# TP2_EJ1_CIRCUIT1_PCB.net
KiCad netlist of a schematic drawn in Altium Designer
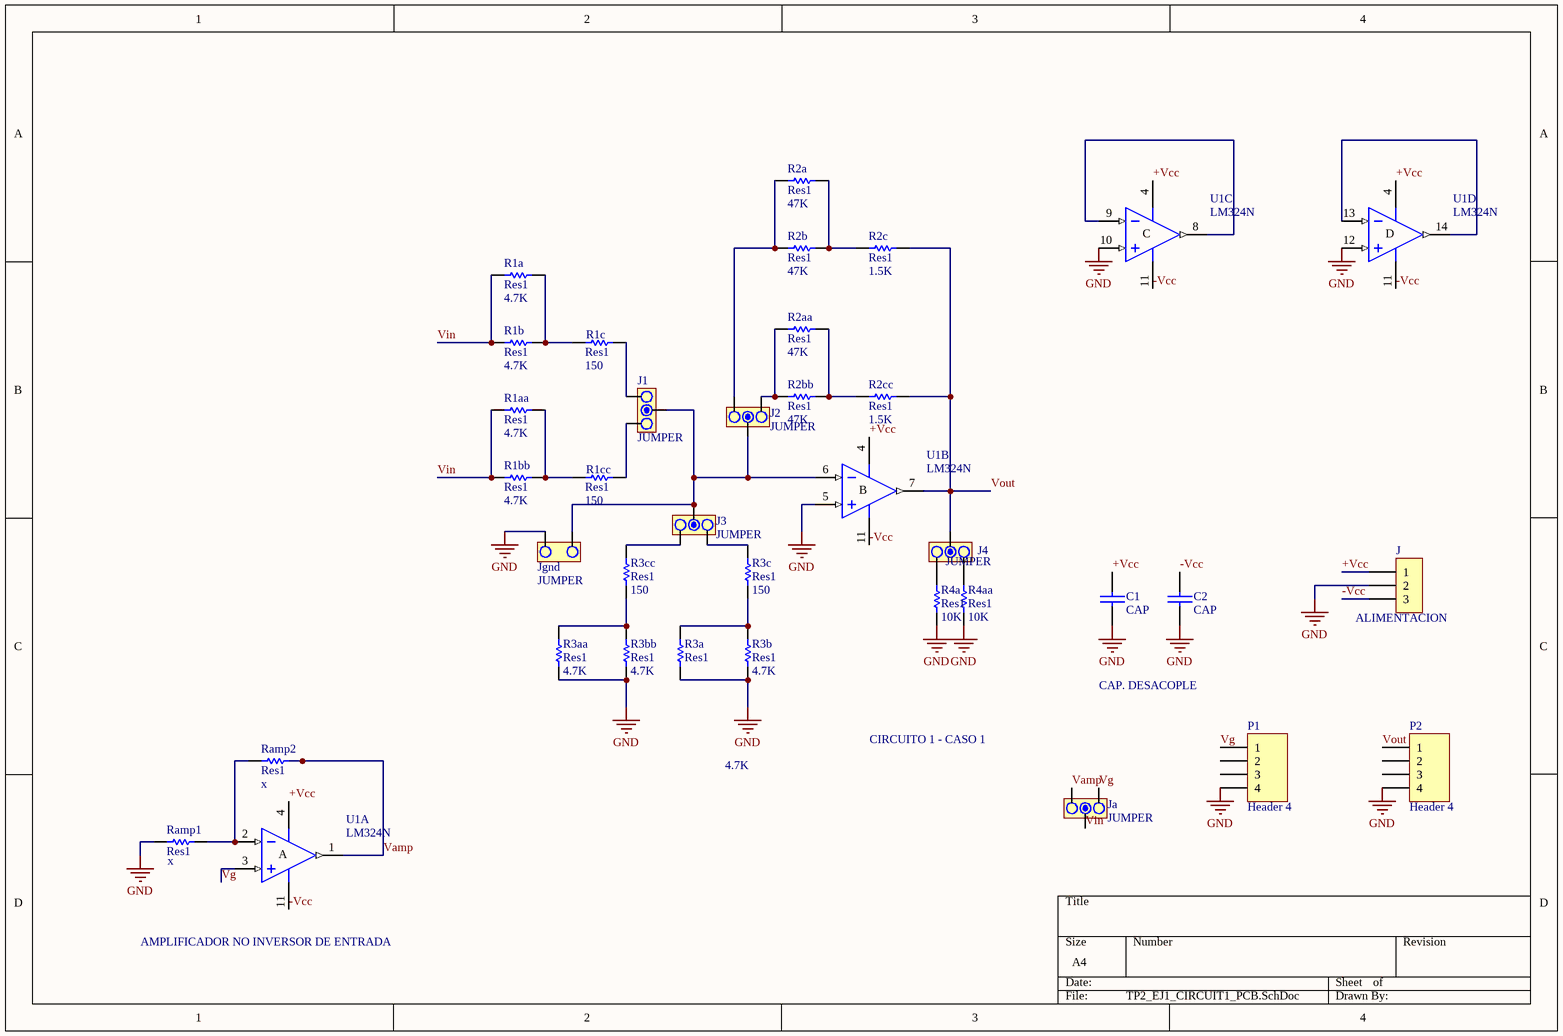
[diagram p0: TP2_EJ1_CIRCUIT1_PCB.SchDoc]

(export (version "E")
  (design (tool "Eeschema 10.0.6"))
  (components
    (comp (ref "C1") (value "CAP") (footprint "CAP200") (libsource (lib "LIBEBAL") (part "CAP")))
    (comp (ref "C2") (value "CAP") (footprint "CAP200") (libsource (lib "LIBEBAL") (part "CAP")))
    (comp (ref "J")
      (value "ALIMENTACION")
      (footprint "BORNERA3")
      (libsource (lib "LIBEBAL") (part "BORNERA 3"))
    )
    (comp (ref "J1")
      (value "JUMPER")
      (footprint "JUMPER3TH")
      (description "TIRA DE PINES 1x3")
      (libsource (lib "") (part "JUMPER3TH_2"))
    )
    (comp (ref "J2")
      (value "JUMPER")
      (footprint "JUMPER3TH")
      (description "TIRA DE PINES 1x3")
      (libsource (lib "") (part "JUMPER3TH_1"))
    )
    (comp (ref "J3")
      (value "JUMPER")
      (footprint "JUMPER3TH")
      (description "TIRA DE PINES 1x3")
      (libsource (lib "LIBEBAL") (part "JUMPER3TH"))
    )
    (comp (ref "J4")
      (value "JUMPER")
      (footprint "JUMPER3TH")
      (description "TIRA DE PINES 1x3")
      (libsource (lib "LIBEBAL") (part "JUMPER3TH"))
    )
    (comp (ref "Ja")
      (value "JUMPER")
      (footprint "JUMPER3TH")
      (description "TIRA DE PINES 1x3")
      (libsource (lib "") (part "JUMPER3TH_1"))
    )
    (comp (ref "Jgnd") (value "JUMPER") (footprint "JUMPER2") (libsource (lib "LIBEBAL") (part "JUMPER")))
    (comp (ref "P1")
      (value "Header 4")
      (footprint "HDR1X4")
      (description "Header, 4-Pin")
      (fields (field (name "PUBLISHER") "Altium Limited"))
      (libsource (lib "Miscellaneous Connectors") (part "Header 4"))
    )
    (comp (ref "P2")
      (value "Header 4")
      (footprint "HDR1X4")
      (description "Header, 4-Pin")
      (fields (field (name "PUBLISHER") "Altium Limited"))
      (libsource (lib "Miscellaneous Connectors") (part "Header 4"))
    )
    (comp (ref "R1a")
      (value "Res1")
      (footprint "AXIAL-0.3")
      (description "Resistor")
      (fields (field (name "ALTIUM_VALUE") "4.7K") (field (name "PUBLISHER") "Altium Limited"))
      (libsource (lib "Miscellaneous Devices") (part "Res1"))
    )
    (comp (ref "R1aa")
      (value "Res1")
      (footprint "AXIAL-0.3")
      (description "Resistor")
      (fields (field (name "ALTIUM_VALUE") "4.7K") (field (name "PUBLISHER") "Altium Limited"))
      (libsource (lib "Miscellaneous Devices") (part "Res1"))
    )
    (comp (ref "R1b")
      (value "Res1")
      (footprint "AXIAL-0.3")
      (description "Resistor")
      (fields (field (name "ALTIUM_VALUE") "4.7K") (field (name "PUBLISHER") "Altium Limited"))
      (libsource (lib "Miscellaneous Devices") (part "Res1"))
    )
    (comp (ref "R1bb")
      (value "Res1")
      (footprint "AXIAL-0.3")
      (description "Resistor")
      (fields (field (name "ALTIUM_VALUE") "4.7K") (field (name "PUBLISHER") "Altium Limited"))
      (libsource (lib "Miscellaneous Devices") (part "Res1"))
    )
    (comp (ref "R1c")
      (value "Res1")
      (footprint "AXIAL-0.3")
      (description "Resistor")
      (fields (field (name "ALTIUM_VALUE") "150") (field (name "PUBLISHER") "Altium Limited"))
      (libsource (lib "Miscellaneous Devices") (part "Res1"))
    )
    (comp (ref "R1cc")
      (value "Res1")
      (footprint "AXIAL-0.3")
      (description "Resistor")
      (fields (field (name "ALTIUM_VALUE") "150") (field (name "PUBLISHER") "Altium Limited"))
      (libsource (lib "Miscellaneous Devices") (part "Res1"))
    )
    (comp (ref "R2a")
      (value "Res1")
      (footprint "AXIAL-0.3")
      (description "Resistor")
      (fields (field (name "ALTIUM_VALUE") "47K") (field (name "PUBLISHER") "Altium Limited"))
      (libsource (lib "Miscellaneous Devices") (part "Res1"))
    )
    (comp (ref "R2aa")
      (value "Res1")
      (footprint "AXIAL-0.3")
      (description "Resistor")
      (fields (field (name "ALTIUM_VALUE") "47K") (field (name "PUBLISHER") "Altium Limited"))
      (libsource (lib "Miscellaneous Devices") (part "Res1"))
    )
    (comp (ref "R2b")
      (value "Res1")
      (footprint "AXIAL-0.3")
      (description "Resistor")
      (fields (field (name "ALTIUM_VALUE") "47K") (field (name "PUBLISHER") "Altium Limited"))
      (libsource (lib "Miscellaneous Devices") (part "Res1"))
    )
    (comp (ref "R2bb")
      (value "Res1")
      (footprint "AXIAL-0.3")
      (description "Resistor")
      (fields (field (name "ALTIUM_VALUE") "47K") (field (name "PUBLISHER") "Altium Limited"))
      (libsource (lib "Miscellaneous Devices") (part "Res1"))
    )
    (comp (ref "R2c")
      (value "Res1")
      (footprint "AXIAL-0.3")
      (description "Resistor")
      (fields (field (name "ALTIUM_VALUE") "1.5K") (field (name "PUBLISHER") "Altium Limited"))
      (libsource (lib "Miscellaneous Devices") (part "Res1"))
    )
    (comp (ref "R2cc")
      (value "Res1")
      (footprint "AXIAL-0.3")
      (description "Resistor")
      (fields (field (name "ALTIUM_VALUE") "1.5K") (field (name "PUBLISHER") "Altium Limited"))
      (libsource (lib "Miscellaneous Devices") (part "Res1"))
    )
    (comp (ref "R3a")
      (value "Res1")
      (footprint "AXIAL-0.3")
      (description "Resistor")
      (fields (field (name "ALTIUM_VALUE") "4.7K") (field (name "PUBLISHER") "Altium Limited"))
      (libsource (lib "Miscellaneous Devices") (part "Res1"))
    )
    (comp (ref "R3aa")
      (value "Res1")
      (footprint "AXIAL-0.3")
      (description "Resistor")
      (fields (field (name "ALTIUM_VALUE") "4.7K") (field (name "PUBLISHER") "Altium Limited"))
      (libsource (lib "Miscellaneous Devices") (part "Res1"))
    )
    (comp (ref "R3b")
      (value "Res1")
      (footprint "AXIAL-0.3")
      (description "Resistor")
      (fields (field (name "ALTIUM_VALUE") "4.7K") (field (name "PUBLISHER") "Altium Limited"))
      (libsource (lib "Miscellaneous Devices") (part "Res1"))
    )
    (comp (ref "R3bb")
      (value "Res1")
      (footprint "AXIAL-0.3")
      (description "Resistor")
      (fields (field (name "ALTIUM_VALUE") "4.7K") (field (name "PUBLISHER") "Altium Limited"))
      (libsource (lib "Miscellaneous Devices") (part "Res1"))
    )
    (comp (ref "R3c")
      (value "Res1")
      (footprint "AXIAL-0.3")
      (description "Resistor")
      (fields (field (name "ALTIUM_VALUE") "150") (field (name "PUBLISHER") "Altium Limited"))
      (libsource (lib "Miscellaneous Devices") (part "Res1"))
    )
    (comp (ref "R3cc")
      (value "Res1")
      (footprint "AXIAL-0.3")
      (description "Resistor")
      (fields (field (name "ALTIUM_VALUE") "150") (field (name "PUBLISHER") "Altium Limited"))
      (libsource (lib "Miscellaneous Devices") (part "Res1"))
    )
    (comp (ref "R4a")
      (value "Res1")
      (footprint "AXIAL-0.3")
      (description "Resistor")
      (fields (field (name "ALTIUM_VALUE") "10K") (field (name "PUBLISHER") "Altium Limited"))
      (libsource (lib "Miscellaneous Devices") (part "Res1"))
    )
    (comp (ref "R4aa")
      (value "Res1")
      (footprint "AXIAL-0.3")
      (description "Resistor")
      (fields (field (name "ALTIUM_VALUE") "10K") (field (name "PUBLISHER") "Altium Limited"))
      (libsource (lib "Miscellaneous Devices") (part "Res1"))
    )
    (comp (ref "Ramp1")
      (value "Res1")
      (footprint "AXIAL-0.3")
      (description "Resistor")
      (fields (field (name "ALTIUM_VALUE") "x") (field (name "PUBLISHER") "Altium Limited"))
      (libsource (lib "Miscellaneous Devices") (part "Res1"))
    )
    (comp (ref "Ramp2")
      (value "Res1")
      (footprint "AXIAL-0.3")
      (description "Resistor")
      (fields (field (name "ALTIUM_VALUE") "x") (field (name "PUBLISHER") "Altium Limited"))
      (libsource (lib "Miscellaneous Devices") (part "Res1"))
    )
    (comp (ref "U1")
      (value "LM324N")
      (footprint "N014")
      (description "Quadruple Operational Amplifier")
      (fields (field (name "PUBLISHER") "Altium Limited"))
      (libsource (lib "TI Operational Amplifier") (part "LM324N"))
    )
  )
  (nets
    (net (code "1") (name "/+Vcc") (class "Default")
      (node (ref "C1") (pin "1") (pinfunction "1_1") (pintype "passive"))
      (node (ref "J") (pin "1") (pinfunction "1_1") (pintype "passive"))
      (node (ref "U1") (pin "4") (pinfunction "V+_4") (pintype "power_in"))
    )
    (net (code "2") (name "/-Vcc") (class "Default")
      (node (ref "C2") (pin "1") (pinfunction "1_1") (pintype "passive"))
      (node (ref "J") (pin "3") (pinfunction "3_3") (pintype "passive"))
      (node (ref "U1") (pin "11") (pinfunction "V-_11") (pintype "power_in"))
    )
    (net (code "3") (name "/Vamp") (class "Default")
      (node (ref "Ja") (pin "1") (pinfunction "1_1") (pintype "passive"))
      (node (ref "Ramp2") (pin "2") (pinfunction "2_2") (pintype "passive"))
      (node (ref "U1") (pin "1") (pinfunction "OUT_1") (pintype "output"))
    )
    (net (code "4") (name "/Vg") (class "Default")
      (node (ref "Ja") (pin "3") (pinfunction "3_3") (pintype "passive"))
      (node (ref "P1") (pin "1") (pinfunction "1_1") (pintype "passive"))
      (node (ref "U1") (pin "3") (pinfunction "IN+_3") (pintype "input"))
    )
    (net (code "5") (name "/Vin") (class "Default")
      (node (ref "Ja") (pin "2") (pinfunction "2_2") (pintype "passive"))
      (node (ref "R1a") (pin "1") (pinfunction "1_1") (pintype "passive"))
      (node (ref "R1aa") (pin "1") (pinfunction "1_1") (pintype "passive"))
      (node (ref "R1b") (pin "1") (pinfunction "1_1") (pintype "passive"))
      (node (ref "R1bb") (pin "1") (pinfunction "1_1") (pintype "passive"))
    )
    (net (code "6") (name "/Vout") (class "Default")
      (node (ref "J4") (pin "2") (pinfunction "2_2") (pintype "passive"))
      (node (ref "P2") (pin "1") (pinfunction "1_1") (pintype "passive"))
      (node (ref "R2c") (pin "2") (pinfunction "2_2") (pintype "passive"))
      (node (ref "R2cc") (pin "2") (pinfunction "2_2") (pintype "passive"))
      (node (ref "U1") (pin "7") (pinfunction "OUT_7") (pintype "output"))
    )
    (net (code "7") (name "GND") (class "Default")
      (node (ref "C1") (pin "2") (pinfunction "2_2") (pintype "passive"))
      (node (ref "C2") (pin "2") (pinfunction "2_2") (pintype "passive"))
      (node (ref "J") (pin "2") (pinfunction "2_2") (pintype "passive"))
      (node (ref "Jgnd") (pin "1") (pinfunction "1_1") (pintype "passive"))
      (node (ref "P1") (pin "4") (pinfunction "4_4") (pintype "passive"))
      (node (ref "P2") (pin "4") (pinfunction "4_4") (pintype "passive"))
      (node (ref "R3a") (pin "1") (pinfunction "1_1") (pintype "passive"))
      (node (ref "R3aa") (pin "1") (pinfunction "1_1") (pintype "passive"))
      (node (ref "R3b") (pin "1") (pinfunction "1_1") (pintype "passive"))
      (node (ref "R3bb") (pin "1") (pinfunction "1_1") (pintype "passive"))
      (node (ref "R4a") (pin "1") (pinfunction "1_1") (pintype "passive"))
      (node (ref "R4aa") (pin "1") (pinfunction "1_1") (pintype "passive"))
      (node (ref "Ramp1") (pin "1") (pinfunction "1_1") (pintype "passive"))
      (node (ref "U1") (pin "10") (pinfunction "IN+_10") (pintype "input"))
      (node (ref "U1") (pin "12") (pinfunction "IN+_12") (pintype "input"))
      (node (ref "U1") (pin "5") (pinfunction "IN+_5") (pintype "input"))
    )
    (net (code "8") (name "Net-(J1-Pad1)") (class "Default")
      (node (ref "J1") (pin "1") (pinfunction "1_1") (pintype "passive"))
      (node (ref "R1cc") (pin "2") (pinfunction "2_2") (pintype "passive"))
    )
    (net (code "9") (name "Net-(J1-Pad3)") (class "Default")
      (node (ref "J1") (pin "3") (pinfunction "3_3") (pintype "passive"))
      (node (ref "R1c") (pin "2") (pinfunction "2_2") (pintype "passive"))
    )
    (net (code "10") (name "Net-(J2-Pad1)") (class "Default")
      (node (ref "J2") (pin "1") (pinfunction "1_1") (pintype "passive"))
      (node (ref "R2a") (pin "1") (pinfunction "1_1") (pintype "passive"))
      (node (ref "R2b") (pin "1") (pinfunction "1_1") (pintype "passive"))
    )
    (net (code "11") (name "Net-(J2-Pad3)") (class "Default")
      (node (ref "J2") (pin "3") (pinfunction "3_3") (pintype "passive"))
      (node (ref "R2aa") (pin "1") (pinfunction "1_1") (pintype "passive"))
      (node (ref "R2bb") (pin "1") (pinfunction "1_1") (pintype "passive"))
    )
    (net (code "12") (name "Net-(J3-Pad1)") (class "Default")
      (node (ref "J3") (pin "1") (pinfunction "1_1") (pintype "passive"))
      (node (ref "R3c") (pin "2") (pinfunction "2_2") (pintype "passive"))
    )
    (net (code "13") (name "Net-(J3-Pad3)") (class "Default")
      (node (ref "J3") (pin "3") (pinfunction "3_3") (pintype "passive"))
      (node (ref "R3cc") (pin "2") (pinfunction "2_2") (pintype "passive"))
    )
    (net (code "14") (name "Net-(J4-Pad1)") (class "Default")
      (node (ref "J4") (pin "1") (pinfunction "1_1") (pintype "passive"))
      (node (ref "R4aa") (pin "2") (pinfunction "2_2") (pintype "passive"))
    )
    (net (code "15") (name "Net-(J4-Pad3)") (class "Default")
      (node (ref "J4") (pin "3") (pinfunction "3_3") (pintype "passive"))
      (node (ref "R4a") (pin "2") (pinfunction "2_2") (pintype "passive"))
    )
    (net (code "16") (name "Net-(R1a-Pad2)") (class "Default")
      (node (ref "R1a") (pin "2") (pinfunction "2_2") (pintype "passive"))
      (node (ref "R1b") (pin "2") (pinfunction "2_2") (pintype "passive"))
      (node (ref "R1c") (pin "1") (pinfunction "1_1") (pintype "passive"))
    )
    (net (code "17") (name "Net-(R1aa-Pad2)") (class "Default")
      (node (ref "R1aa") (pin "2") (pinfunction "2_2") (pintype "passive"))
      (node (ref "R1bb") (pin "2") (pinfunction "2_2") (pintype "passive"))
      (node (ref "R1cc") (pin "1") (pinfunction "1_1") (pintype "passive"))
    )
    (net (code "18") (name "Net-(R2a-Pad2)") (class "Default")
      (node (ref "R2a") (pin "2") (pinfunction "2_2") (pintype "passive"))
      (node (ref "R2b") (pin "2") (pinfunction "2_2") (pintype "passive"))
      (node (ref "R2c") (pin "1") (pinfunction "1_1") (pintype "passive"))
    )
    (net (code "19") (name "Net-(R2aa-Pad2)") (class "Default")
      (node (ref "R2aa") (pin "2") (pinfunction "2_2") (pintype "passive"))
      (node (ref "R2bb") (pin "2") (pinfunction "2_2") (pintype "passive"))
      (node (ref "R2cc") (pin "1") (pinfunction "1_1") (pintype "passive"))
    )
    (net (code "20") (name "Net-(R3a-Pad2)") (class "Default")
      (node (ref "R3a") (pin "2") (pinfunction "2_2") (pintype "passive"))
      (node (ref "R3b") (pin "2") (pinfunction "2_2") (pintype "passive"))
      (node (ref "R3c") (pin "1") (pinfunction "1_1") (pintype "passive"))
    )
    (net (code "21") (name "Net-(R3aa-Pad2)") (class "Default")
      (node (ref "R3aa") (pin "2") (pinfunction "2_2") (pintype "passive"))
      (node (ref "R3bb") (pin "2") (pinfunction "2_2") (pintype "passive"))
      (node (ref "R3cc") (pin "1") (pinfunction "1_1") (pintype "passive"))
    )
    (net (code "22") (name "Net-(U1A-IN-)") (class "Default")
      (node (ref "Ramp1") (pin "2") (pinfunction "2_2") (pintype "passive"))
      (node (ref "Ramp2") (pin "1") (pinfunction "1_1") (pintype "passive"))
      (node (ref "U1") (pin "2") (pinfunction "IN-_2") (pintype "input"))
    )
    (net (code "23") (name "Net-(U1B-IN-)") (class "Default")
      (node (ref "J1") (pin "2") (pinfunction "2_2") (pintype "passive"))
      (node (ref "J2") (pin "2") (pinfunction "2_2") (pintype "passive"))
      (node (ref "J3") (pin "2") (pinfunction "2_2") (pintype "passive"))
      (node (ref "Jgnd") (pin "2") (pinfunction "2_2") (pintype "passive"))
      (node (ref "U1") (pin "6") (pinfunction "IN-_6") (pintype "input"))
    )
    (net (code "24") (name "Net-(U1C-IN-)") (class "Default")
      (node (ref "U1") (pin "8") (pinfunction "OUT_8") (pintype "output"))
      (node (ref "U1") (pin "9") (pinfunction "IN-_9") (pintype "input"))
    )
    (net (code "25") (name "Net-(U1D-IN-)") (class "Default")
      (node (ref "U1") (pin "13") (pinfunction "IN-_13") (pintype "input"))
      (node (ref "U1") (pin "14") (pinfunction "OUT_14") (pintype "output"))
    )
    (net (code "26") (name "unconnected-(P1-Pad2)") (class "Default")
      (node (ref "P1") (pin "2") (pinfunction "2_2") (pintype "passive"))
    )
    (net (code "27") (name "unconnected-(P1-Pad3)") (class "Default")
      (node (ref "P1") (pin "3") (pinfunction "3_3") (pintype "passive"))
    )
    (net (code "28") (name "unconnected-(P2-Pad2)") (class "Default")
      (node (ref "P2") (pin "2") (pinfunction "2_2") (pintype "passive"))
    )
    (net (code "29") (name "unconnected-(P2-Pad3)") (class "Default")
      (node (ref "P2") (pin "3") (pinfunction "3_3") (pintype "passive"))
    )
  )
)
